# level-shift_rpi-atmel.net
KiCad netlist of a schematic drawn in EAGLE
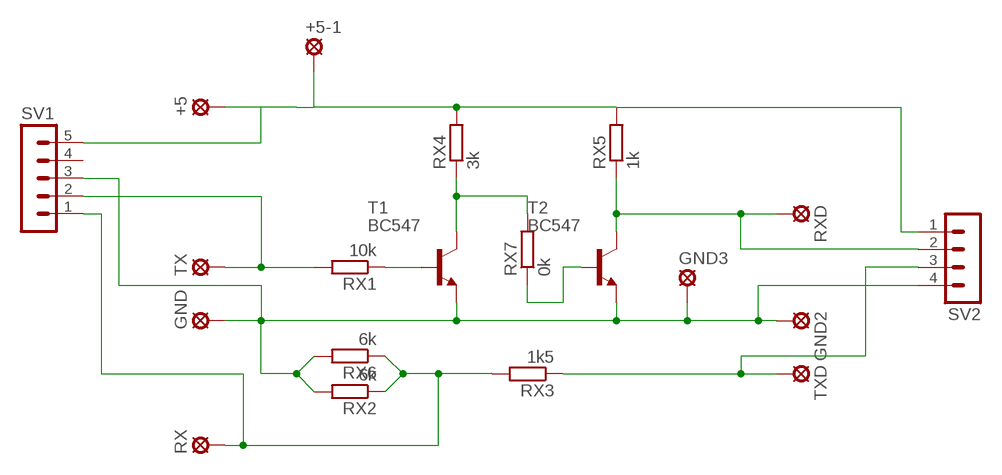
[diagram p0: schematic, sheet 1]

(export (version "E")
  (design (tool "Eeschema 10.0.6"))
  (components
    (comp (ref "+5")
      (value "LSP10")
      (footprint "eagle-import:LSP10")
      (libsource (lib "eagle-import") (part "LSP10"))
    )
    (comp (ref "+5-1")
      (value "LSP10")
      (footprint "eagle-import:LSP10")
      (libsource (lib "eagle-import") (part "LSP10"))
    )
    (comp (ref "GND")
      (value "LSP10")
      (footprint "eagle-import:LSP10")
      (libsource (lib "eagle-import") (part "LSP10"))
    )
    (comp (ref "GND2")
      (value "LSP10")
      (footprint "eagle-import:LSP10")
      (libsource (lib "eagle-import") (part "LSP10"))
    )
    (comp (ref "GND3")
      (value "LSP10")
      (footprint "eagle-import:LSP10")
      (libsource (lib "eagle-import") (part "LSP10"))
    )
    (comp (ref "RX")
      (value "LSP10")
      (footprint "eagle-import:LSP10")
      (libsource (lib "eagle-import") (part "LSP10"))
    )
    (comp (ref "RX1")
      (value "10k")
      (footprint "eagle-import:0204_5")
      (libsource (lib "eagle-import") (part "R-EU_0204/5"))
    )
    (comp (ref "RX2")
      (value "6k")
      (footprint "eagle-import:0207_5V")
      (libsource (lib "eagle-import") (part "R-EU_0207/5V"))
    )
    (comp (ref "RX3")
      (value "1k5")
      (footprint "eagle-import:0207_5V")
      (libsource (lib "eagle-import") (part "R-EU_0207/5V"))
    )
    (comp (ref "RX4")
      (value "3k")
      (footprint "eagle-import:0207_7")
      (libsource (lib "eagle-import") (part "R-EU_0207/7"))
    )
    (comp (ref "RX5")
      (value "1k")
      (footprint "eagle-import:0204_7")
      (libsource (lib "eagle-import") (part "R-EU_0204/7"))
    )
    (comp (ref "RX6")
      (value "6k")
      (footprint "eagle-import:0207_5V")
      (libsource (lib "eagle-import") (part "R-EU_0207/5V"))
    )
    (comp (ref "RX7")
      (value "0k")
      (footprint "eagle-import:0204_5")
      (libsource (lib "eagle-import") (part "R-EU_0204/5"))
    )
    (comp (ref "RXD")
      (value "LSP10")
      (footprint "eagle-import:LSP10")
      (libsource (lib "eagle-import") (part "LSP10"))
    )
    (comp (ref "SV1")
      (value "MA05-1")
      (footprint "eagle-import:MA05-1")
      (libsource (lib "eagle-import") (part "MA05-1"))
    )
    (comp (ref "SV2")
      (value "MA04-1")
      (footprint "eagle-import:MA04-1")
      (libsource (lib "eagle-import") (part "MA04-1"))
    )
    (comp (ref "T1")
      (value "BC547")
      (footprint "eagle-import:TO92")
      (libsource (lib "eagle-import") (part "BC547"))
    )
    (comp (ref "T2")
      (value "BC547")
      (footprint "eagle-import:TO92")
      (libsource (lib "eagle-import") (part "BC547"))
    )
    (comp (ref "TX")
      (value "LSP10")
      (footprint "eagle-import:LSP10")
      (libsource (lib "eagle-import") (part "LSP10"))
    )
    (comp (ref "TXD")
      (value "LSP10")
      (footprint "eagle-import:LSP10")
      (libsource (lib "eagle-import") (part "LSP10"))
    )
  )
  (nets
    (net (code "1") (name "Net-(+5-1-PadMP)") (class "Default")
      (node (ref "+5") (pin "MP") (pinfunction "MP_MP") (pintype "passive"))
      (node (ref "+5-1") (pin "MP") (pinfunction "MP_MP") (pintype "passive"))
      (node (ref "RX4") (pin "2") (pinfunction "2_2") (pintype "passive"))
      (node (ref "RX5") (pin "2") (pinfunction "2_2") (pintype "passive"))
      (node (ref "SV1") (pin "5") (pinfunction "5_5") (pintype "passive"))
      (node (ref "SV2") (pin "1") (pinfunction "1_1") (pintype "passive"))
    )
    (net (code "2") (name "Net-(RX-PadMP)") (class "Default")
      (node (ref "RX") (pin "MP") (pinfunction "MP_MP") (pintype "passive"))
      (node (ref "RX2") (pin "1") (pinfunction "1_1") (pintype "passive"))
      (node (ref "RX3") (pin "2") (pinfunction "2_2") (pintype "passive"))
      (node (ref "RX6") (pin "1") (pinfunction "1_1") (pintype "passive"))
      (node (ref "SV1") (pin "1") (pinfunction "1_1") (pintype "passive"))
    )
    (net (code "3") (name "Net-(RX1-Pad2)") (class "Default")
      (node (ref "RX1") (pin "2") (pinfunction "2_2") (pintype "passive"))
      (node (ref "SV1") (pin "2") (pinfunction "2_2") (pintype "passive"))
      (node (ref "TX") (pin "MP") (pinfunction "MP_MP") (pintype "passive"))
    )
    (net (code "4") (name "Net-(RX3-Pad1)") (class "Default")
      (node (ref "RX3") (pin "1") (pinfunction "1_1") (pintype "passive"))
      (node (ref "SV2") (pin "3") (pinfunction "3_3") (pintype "passive"))
      (node (ref "TXD") (pin "MP") (pinfunction "MP_MP") (pintype "passive"))
    )
    (net (code "5") (name "Net-(T1-B)") (class "Default")
      (node (ref "RX1") (pin "1") (pinfunction "1_1") (pintype "passive"))
      (node (ref "T1") (pin "2") (pinfunction "B_2") (pintype "passive"))
    )
    (net (code "6") (name "Net-(T1-C)") (class "Default")
      (node (ref "RX4") (pin "1") (pinfunction "1_1") (pintype "passive"))
      (node (ref "RX7") (pin "2") (pinfunction "2_2") (pintype "passive"))
      (node (ref "T1") (pin "3") (pinfunction "C_3") (pintype "passive"))
    )
    (net (code "7") (name "Net-(T1-E)") (class "Default")
      (node (ref "GND") (pin "MP") (pinfunction "MP_MP") (pintype "passive"))
      (node (ref "GND2") (pin "MP") (pinfunction "MP_MP") (pintype "passive"))
      (node (ref "GND3") (pin "MP") (pinfunction "MP_MP") (pintype "passive"))
      (node (ref "RX2") (pin "2") (pinfunction "2_2") (pintype "passive"))
      (node (ref "RX6") (pin "2") (pinfunction "2_2") (pintype "passive"))
      (node (ref "SV1") (pin "3") (pinfunction "3_3") (pintype "passive"))
      (node (ref "SV2") (pin "4") (pinfunction "4_4") (pintype "passive"))
      (node (ref "T1") (pin "1") (pinfunction "E_1") (pintype "passive"))
      (node (ref "T2") (pin "1") (pinfunction "E_1") (pintype "passive"))
    )
    (net (code "8") (name "Net-(T2-B)") (class "Default")
      (node (ref "RX7") (pin "1") (pinfunction "1_1") (pintype "passive"))
      (node (ref "T2") (pin "2") (pinfunction "B_2") (pintype "passive"))
    )
    (net (code "9") (name "Net-(T2-C)") (class "Default")
      (node (ref "RX5") (pin "1") (pinfunction "1_1") (pintype "passive"))
      (node (ref "RXD") (pin "MP") (pinfunction "MP_MP") (pintype "passive"))
      (node (ref "SV2") (pin "2") (pinfunction "2_2") (pintype "passive"))
      (node (ref "T2") (pin "3") (pinfunction "C_3") (pintype "passive"))
    )
    (net (code "10") (name "unconnected-(SV1-Pad4)") (class "Default")
      (node (ref "SV1") (pin "4") (pinfunction "4_4") (pintype "passive"))
    )
  )
)
